# rtd_interface_MAX31865.net
KiCad netlist of a schematic drawn in Altium Designer
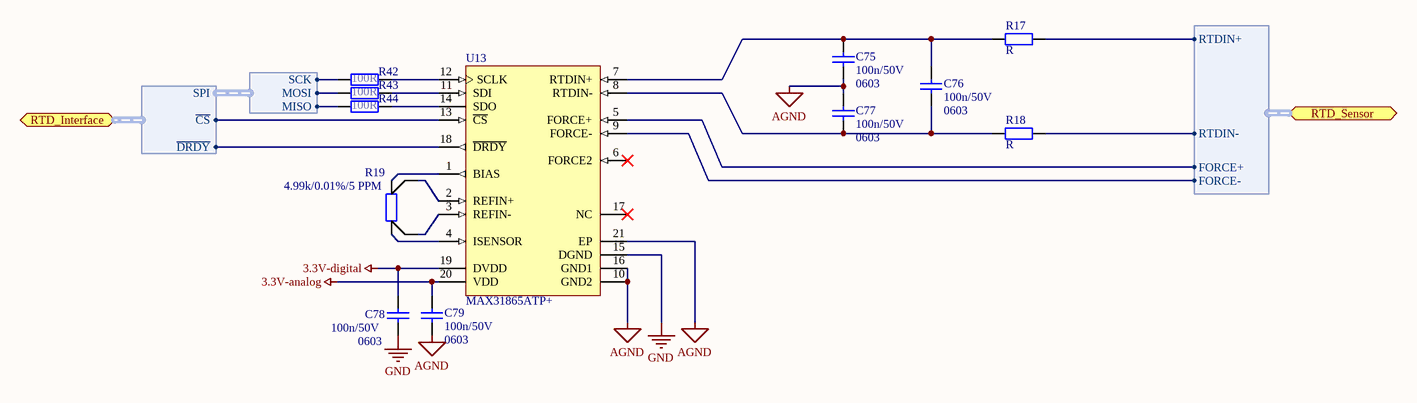
[diagram p0: rtd_interface_MAX31865.SchDoc]

(export (version "E")
  (design (tool "Eeschema 10.0.6"))
  (components
    (comp (ref "C75")
      (value "100n/50V")
      (footprint "SMD_Capacitor_0603")
      (description "Ceramic Cap Kemet COTS 100n/50V X7R 0603")
      (fields
        (field (name "MANUFACTURER") "Kemet")
        (field (name "MANUFACTURERPARTNUMBER") "C0603T104K5RALTU")
        (field (name "PACKAGE") "0603")
      )
      (libsource (lib "capacitors") (part "Cer_C0603T104K5RALTU"))
    )
    (comp (ref "C76")
      (value "100n/50V")
      (footprint "SMD_Capacitor_0603")
      (description "Ceramic Cap Kemet COTS 100n/50V X7R 0603")
      (fields
        (field (name "MANUFACTURER") "Kemet")
        (field (name "MANUFACTURERPARTNUMBER") "C0603T104K5RALTU")
        (field (name "PACKAGE") "0603")
      )
      (libsource (lib "capacitors") (part "Cer_C0603T104K5RALTU"))
    )
    (comp (ref "C77")
      (value "100n/50V")
      (footprint "SMD_Capacitor_0603")
      (description "Ceramic Cap Kemet COTS 100n/50V X7R 0603")
      (fields
        (field (name "MANUFACTURER") "Kemet")
        (field (name "MANUFACTURERPARTNUMBER") "C0603T104K5RALTU")
        (field (name "PACKAGE") "0603")
      )
      (libsource (lib "capacitors") (part "Cer_C0603T104K5RALTU"))
    )
    (comp (ref "C78")
      (value "100n/50V")
      (footprint "SMD_Capacitor_0603")
      (description "Ceramic Cap Kemet COTS 100n/50V X7R 0603")
      (fields
        (field (name "MANUFACTURER") "Kemet")
        (field (name "MANUFACTURERPARTNUMBER") "C0603T104K5RALTU")
        (field (name "PACKAGE") "0603")
      )
      (libsource (lib "capacitors") (part "Cer_C0603T104K5RALTU"))
    )
    (comp (ref "C79")
      (value "100n/50V")
      (footprint "SMD_Capacitor_0603")
      (description "Ceramic Cap Kemet COTS 100n/50V X7R 0603")
      (fields
        (field (name "MANUFACTURER") "Kemet")
        (field (name "MANUFACTURERPARTNUMBER") "C0603T104K5RALTU")
        (field (name "PACKAGE") "0603")
      )
      (libsource (lib "capacitors") (part "Cer_C0603T104K5RALTU"))
    )
    (comp (ref "R17")
      (value "R")
      (footprint "0603")
      (description "Generic resistor")
      (libsource (lib "GG") (part "Res"))
    )
    (comp (ref "R18")
      (value "R")
      (footprint "0603")
      (description "Generic resistor")
      (libsource (lib "GG") (part "Res"))
    )
    (comp (ref "R19")
      (value "4.99k/0.01%/5 PPM")
      (footprint "0603_shunt")
      (description "Generic shunt resistor")
      (libsource (lib "GG") (part "Res_Shunt"))
    )
    (comp (ref "R42")
      (value "100R")
      (footprint "0603")
      (description "Generic resistor")
      (libsource (lib "GG") (part "Res"))
    )
    (comp (ref "R43")
      (value "100R")
      (footprint "0603")
      (description "Generic resistor")
      (libsource (lib "GG") (part "Res"))
    )
    (comp (ref "R44")
      (value "100R")
      (footprint "0603")
      (description "Generic resistor")
      (libsource (lib "GG") (part "Res"))
    )
    (comp (ref "U13")
      (value "MAX31865ATP+")
      (footprint "MAXM-T2055+5_M")
      (fields (field (name "GENERIC PART NUMBER") "MAX31865"))
      (libsource (lib "Maxim Sensors") (part "MAX31865ATP+"))
    )
  )
  (nets
    (net (code "4") (name "/FORCE+") (class "Default")
      (node (ref "U13") (pin "5") (pinfunction "FORCE+_5") (pintype "input"))
    )
    (net (code "5") (name "/FORCE-") (class "Default")
      (node (ref "U13") (pin "9") (pinfunction "FORCE-_9") (pintype "input"))
    )
    (net (code "6") (name "/MISO") (class "Default")
      (node (ref "R44") (pin "1") (pinfunction "1_1") (pintype "passive"))
    )
    (net (code "7") (name "/MOSI") (class "Default")
      (node (ref "R43") (pin "1") (pinfunction "1_1") (pintype "passive"))
    )
    (net (code "8") (name "/RTDIN+") (class "Default")
      (node (ref "R17") (pin "2") (pinfunction "2_2") (pintype "passive"))
    )
    (net (code "9") (name "/RTDIN-") (class "Default")
      (node (ref "R18") (pin "2") (pinfunction "2_2") (pintype "passive"))
    )
    (net (code "10") (name "/SCK") (class "Default")
      (node (ref "R42") (pin "1") (pinfunction "1_1") (pintype "passive"))
    )
    (net (code "14") (name "/~{CS}") (class "Default")
      (node (ref "U13") (pin "13") (pinfunction "~{CS}_13") (pintype "input"))
    )
    (net (code "15") (name "/~{DRDY}") (class "Default")
      (node (ref "U13") (pin "18") (pinfunction "~{DRDY}_18") (pintype "output"))
    )
    (net (code "16") (name "3.3V-analog") (class "Default")
      (node (ref "C79") (pin "1") (pinfunction "1_1") (pintype "passive"))
      (node (ref "U13") (pin "20") (pinfunction "VDD_20") (pintype "power_in"))
    )
    (net (code "17") (name "3.3V-digital") (class "Default")
      (node (ref "C78") (pin "1") (pinfunction "1_1") (pintype "passive"))
      (node (ref "U13") (pin "19") (pinfunction "DVDD_19") (pintype "power_in"))
    )
    (net (code "18") (name "AGND") (class "Default")
      (node (ref "C75") (pin "1") (pinfunction "1_1") (pintype "passive"))
      (node (ref "C77") (pin "2") (pinfunction "2_2") (pintype "passive"))
      (node (ref "C79") (pin "2") (pinfunction "2_2") (pintype "passive"))
      (node (ref "U13") (pin "10") (pinfunction "GND2_10") (pintype "power_in"))
      (node (ref "U13") (pin "16") (pinfunction "GND1_16") (pintype "power_in"))
      (node (ref "U13") (pin "21") (pinfunction "EP_21") (pintype "power_in"))
    )
    (net (code "19") (name "GND") (class "Default")
      (node (ref "C78") (pin "2") (pinfunction "2_2") (pintype "passive"))
      (node (ref "U13") (pin "15") (pinfunction "DGND_15") (pintype "power_in"))
    )
    (net (code "20") (name "Net-(U13-BIAS)") (class "Default")
      (node (ref "R19") (pin "1") (pinfunction "1_1") (pintype "passive"))
      (node (ref "U13") (pin "1") (pinfunction "BIAS_1") (pintype "output"))
    )
    (net (code "21") (name "Net-(U13-ISENSOR)") (class "Default")
      (node (ref "R19") (pin "4") (pinfunction "4_4") (pintype "passive"))
      (node (ref "U13") (pin "4") (pinfunction "ISENSOR_4") (pintype "input"))
    )
    (net (code "22") (name "Net-(U13-REFIN+)") (class "Default")
      (node (ref "R19") (pin "2") (pinfunction "2_2") (pintype "passive"))
      (node (ref "U13") (pin "2") (pinfunction "REFIN+_2") (pintype "input"))
    )
    (net (code "23") (name "Net-(U13-REFIN-)") (class "Default")
      (node (ref "R19") (pin "3") (pinfunction "3_3") (pintype "passive"))
      (node (ref "U13") (pin "3") (pinfunction "REFIN-_3") (pintype "input"))
    )
    (net (code "24") (name "Net-(U13-RTDIN+)") (class "Default")
      (node (ref "C75") (pin "2") (pinfunction "2_2") (pintype "passive"))
      (node (ref "C76") (pin "2") (pinfunction "2_2") (pintype "passive"))
      (node (ref "R17") (pin "1") (pinfunction "1_1") (pintype "passive"))
      (node (ref "U13") (pin "7") (pinfunction "RTDIN+_7") (pintype "input"))
    )
    (net (code "25") (name "Net-(U13-RTDIN-)") (class "Default")
      (node (ref "C76") (pin "1") (pinfunction "1_1") (pintype "passive"))
      (node (ref "C77") (pin "1") (pinfunction "1_1") (pintype "passive"))
      (node (ref "R18") (pin "1") (pinfunction "1_1") (pintype "passive"))
      (node (ref "U13") (pin "8") (pinfunction "RTDIN-_8") (pintype "input"))
    )
    (net (code "26") (name "Net-(U13-SCLK)") (class "Default")
      (node (ref "R42") (pin "2") (pinfunction "2_2") (pintype "passive"))
      (node (ref "U13") (pin "12") (pinfunction "SCLK_12") (pintype "input"))
    )
    (net (code "27") (name "Net-(U13-SDI)") (class "Default")
      (node (ref "R43") (pin "2") (pinfunction "2_2") (pintype "passive"))
      (node (ref "U13") (pin "11") (pinfunction "SDI_11") (pintype "input"))
    )
    (net (code "28") (name "Net-(U13-SDO)") (class "Default")
      (node (ref "R44") (pin "2") (pinfunction "2_2") (pintype "passive"))
      (node (ref "U13") (pin "14") (pinfunction "SDO_14") (pintype "tri_state"))
    )
    (net (code "29") (name "unconnected-(U13-FORCE2-Pad6)") (class "Default")
      (node (ref "U13") (pin "6") (pinfunction "FORCE2_6") (pintype "input+no_connect"))
    )
    (net (code "30") (name "unconnected-(U13-NC-Pad17)") (class "Default")
      (node (ref "U13") (pin "17") (pinfunction "NC_17") (pintype "passive+no_connect"))
    )
  )
)
